# task.net
KiCad netlist of a schematic drawn in Altium Designer
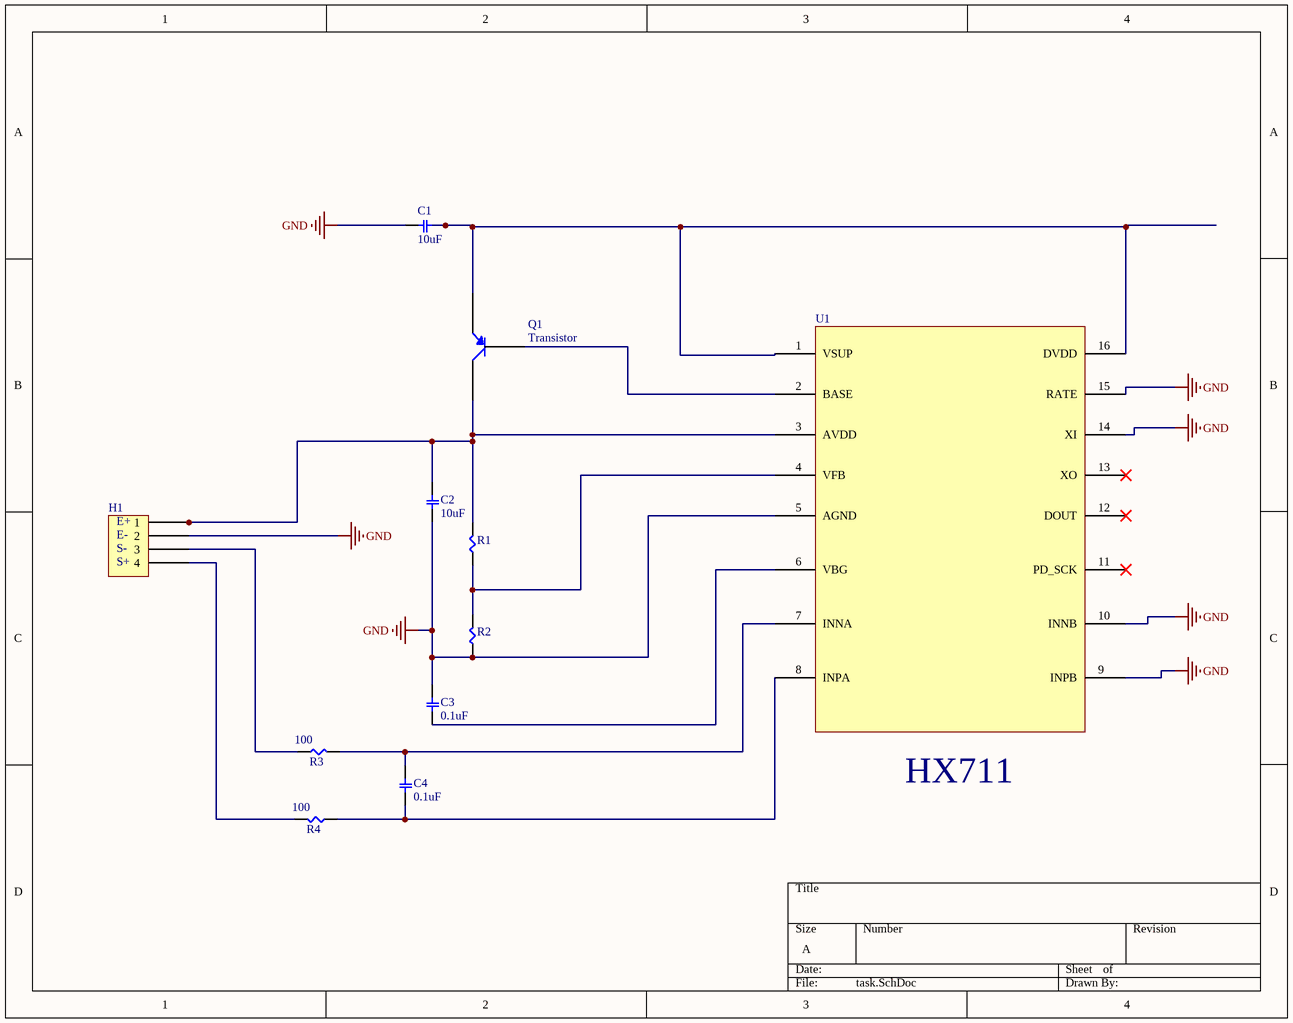
[diagram p0: task.SchDoc]

(export (version "E")
  (design (tool "Eeschema 10.0.6"))
  (components
    (comp (ref "C1")
      (value "10uF")
      (footprint "Capacitor - duplicate")
      (libsource (lib "task_Schlib") (part "Capacitor"))
    )
    (comp (ref "C2")
      (value "10uF")
      (footprint "Capacitor - duplicate")
      (libsource (lib "task_Schlib") (part "Capacitor"))
    )
    (comp (ref "C3")
      (value "0.1uF")
      (footprint "Capacitor - duplicate")
      (libsource (lib "task_Schlib") (part "Capacitor"))
    )
    (comp (ref "C4")
      (value "0.1uF")
      (footprint "Capacitor - duplicate")
      (libsource (lib "task_Schlib") (part "Capacitor"))
    )
    (comp (ref "H1")
      (value "Header")
      (footprint "Edge Connector")
      (libsource (lib "task_Schlib") (part "Header"))
    )
    (comp (ref "Q1")
      (value "Transistor")
      (footprint "Transistor")
      (libsource (lib "task_Schlib") (part "Transistor"))
    )
    (comp (ref "R1")
      (value "resistance")
      (footprint "Resistor")
      (libsource (lib "task_Schlib") (part "resistance"))
    )
    (comp (ref "R2")
      (value "resistance")
      (footprint "Resistor")
      (libsource (lib "task_Schlib") (part "resistance"))
    )
    (comp (ref "R3") (value "100") (footprint "Resistor") (libsource (lib "task_Schlib") (part "resistance")))
    (comp (ref "R4") (value "100") (footprint "Resistor") (libsource (lib "task_Schlib") (part "resistance")))
    (comp (ref "U1")
      (value "hx711")
      (footprint "SOP16")
      (fields
        (field (name "MANUFACTURER") "Avia Semicon (Xiamen)")
        (field (name "MANUFACTURER PART") "HX711")
      )
      (libsource (lib "task_Schlib") (part "hx711"))
    )
  )
  (nets
    (net (code "1") (name "GND") (class "Default")
      (node (ref "C1") (pin "1") (pinfunction "1_1") (pintype "passive"))
      (node (ref "C2") (pin "1") (pinfunction "1_1") (pintype "passive"))
      (node (ref "C3") (pin "2") (pinfunction "2_2") (pintype "passive"))
      (node (ref "H1") (pin "2") (pinfunction "2_2") (pintype "passive"))
      (node (ref "R2") (pin "1") (pinfunction "1_1") (pintype "passive"))
      (node (ref "U1") (pin "10") (pinfunction "INNB_10") (pintype "passive"))
      (node (ref "U1") (pin "14") (pinfunction "XI_14") (pintype "passive"))
      (node (ref "U1") (pin "15") (pinfunction "RATE_15") (pintype "passive"))
      (node (ref "U1") (pin "5") (pinfunction "AGND_5") (pintype "passive"))
      (node (ref "U1") (pin "9") (pinfunction "INPB_9") (pintype "passive"))
    )
    (net (code "2") (name "Net-(H1-Pad3)") (class "Default")
      (node (ref "H1") (pin "3") (pinfunction "3_3") (pintype "passive"))
      (node (ref "R3") (pin "1") (pinfunction "1_1") (pintype "passive"))
    )
    (net (code "3") (name "Net-(H1-Pad4)") (class "Default")
      (node (ref "H1") (pin "4") (pinfunction "4_4") (pintype "passive"))
      (node (ref "R4") (pin "2") (pinfunction "2_2") (pintype "passive"))
    )
    (net (code "4") (name "Net-(Q1-1)") (class "Default")
      (node (ref "C1") (pin "2") (pinfunction "2_2") (pintype "passive"))
      (node (ref "Q1") (pin "G") (pinfunction "1_G") (pintype "passive"))
      (node (ref "U1") (pin "1") (pinfunction "VSUP_1") (pintype "passive"))
      (node (ref "U1") (pin "16") (pinfunction "DVDD_16") (pintype "passive"))
    )
    (net (code "5") (name "Net-(Q1-2)") (class "Default")
      (node (ref "Q1") (pin "D") (pinfunction "2_D") (pintype "passive"))
      (node (ref "U1") (pin "2") (pinfunction "BASE_2") (pintype "passive"))
    )
    (net (code "6") (name "Net-(Q1-3)") (class "Default")
      (node (ref "C2") (pin "2") (pinfunction "2_2") (pintype "passive"))
      (node (ref "H1") (pin "1") (pinfunction "1_1") (pintype "passive"))
      (node (ref "Q1") (pin "S") (pinfunction "3_S") (pintype "passive"))
      (node (ref "R1") (pin "2") (pinfunction "2_2") (pintype "passive"))
      (node (ref "U1") (pin "3") (pinfunction "AVDD_3") (pintype "passive"))
    )
    (net (code "7") (name "Net-(U1-INNA)") (class "Default")
      (node (ref "C4") (pin "2") (pinfunction "2_2") (pintype "passive"))
      (node (ref "R3") (pin "2") (pinfunction "2_2") (pintype "passive"))
      (node (ref "U1") (pin "7") (pinfunction "INNA_7") (pintype "passive"))
    )
    (net (code "8") (name "Net-(U1-INPA)") (class "Default")
      (node (ref "C4") (pin "1") (pinfunction "1_1") (pintype "passive"))
      (node (ref "R4") (pin "1") (pinfunction "1_1") (pintype "passive"))
      (node (ref "U1") (pin "8") (pinfunction "INPA_8") (pintype "passive"))
    )
    (net (code "9") (name "Net-(U1-VBG)") (class "Default")
      (node (ref "C3") (pin "1") (pinfunction "1_1") (pintype "passive"))
      (node (ref "U1") (pin "6") (pinfunction "VBG_6") (pintype "passive"))
    )
    (net (code "10") (name "Net-(U1-VFB)") (class "Default")
      (node (ref "R1") (pin "1") (pinfunction "1_1") (pintype "passive"))
      (node (ref "R2") (pin "2") (pinfunction "2_2") (pintype "passive"))
      (node (ref "U1") (pin "4") (pinfunction "VFB_4") (pintype "passive"))
    )
    (net (code "11") (name "unconnected-(U1-DOUT-Pad12)") (class "Default")
      (node (ref "U1") (pin "12") (pinfunction "DOUT_12") (pintype "passive+no_connect"))
    )
    (net (code "12") (name "unconnected-(U1-PD_SCK-Pad11)") (class "Default")
      (node (ref "U1") (pin "11") (pinfunction "PD_SCK_11") (pintype "passive+no_connect"))
    )
    (net (code "13") (name "unconnected-(U1-XO-Pad13)") (class "Default")
      (node (ref "U1") (pin "13") (pinfunction "XO_13") (pintype "passive+no_connect"))
    )
  )
)
